# Sheetlaba1.net
KiCad netlist of a schematic drawn in Altium Designer
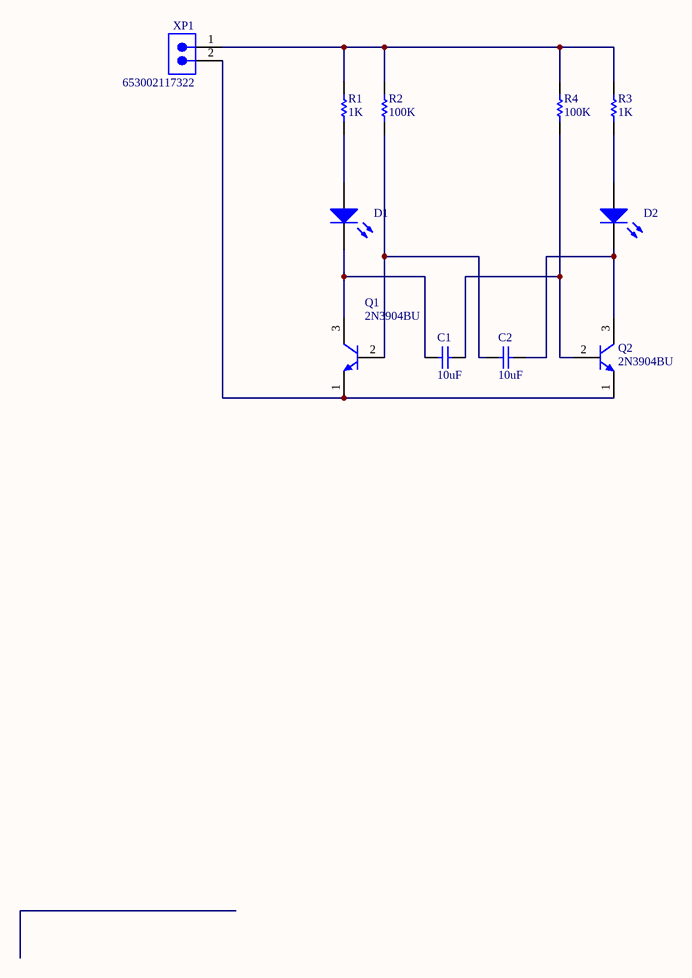
[diagram p0: Sheetlaba1.SchDoc]

(export (version "E")
  (design (tool "Eeschema 10.0.6"))
  (components
    (comp (ref "C1")
      (value "10uF")
      (description "Capacitor")
      (libsource (lib "Simulation Generic Components") (part "Capacitor"))
    )
    (comp (ref "C2")
      (value "10uF")
      (description "Capacitor")
      (libsource (lib "Simulation Generic Components") (part "Capacitor"))
    )
    (comp (ref "D1")
      (value "Light-Emitting Diode")
      (libsource (lib "Simulation Generic Components") (part "LED"))
    )
    (comp (ref "D2")
      (value "Light-Emitting Diode")
      (libsource (lib "Simulation Generic Components") (part "LED"))
    )
    (comp (ref "Q1")
      (value "2N3904BU")
      (footprint "FAIR-TO-92")
      (description "NPN General-Purpose Amplifier, 40 V VCEO, 0.2 A, -55 to 150 degC, 2-Pin TO-92, RoHS, Bulk")
      (fields (field (name "MANUFACTURER") "FairchildSemiconductor"))
      (libsource (lib "Altium Content Vault") (part "NPN-E1B2C3-3"))
    )
    (comp (ref "Q2")
      (value "2N3904BU")
      (footprint "FAIR-TO-92")
      (description "NPN General-Purpose Amplifier, 40 V VCEO, 0.2 A, -55 to 150 degC, 2-Pin TO-92, RoHS, Bulk")
      (fields (field (name "MANUFACTURER") "FairchildSemiconductor"))
      (libsource (lib "Altium Content Vault") (part "NPN-E1B2C3-3"))
    )
    (comp (ref "R1")
      (value "1K")
      (description "Resistor")
      (libsource (lib "Simulation Generic Components") (part "Resistor"))
    )
    (comp (ref "R2")
      (value "100K")
      (description "Resistor")
      (libsource (lib "Simulation Generic Components") (part "Resistor"))
    )
    (comp (ref "R3")
      (value "1K")
      (description "Resistor")
      (libsource (lib "Simulation Generic Components") (part "Resistor"))
    )
    (comp (ref "R4")
      (value "100K")
      (description "Resistor")
      (libsource (lib "Simulation Generic Components") (part "Resistor"))
    )
    (comp (ref "XP1")
      (value "653002117322")
      (footprint "653002117322")
      (description "Conn, R/A Header, 2Pos, 1Row, 1.25Mm Rohs Compliant: Yes")
      (libsource (lib "Altium Content Vault") (part "Header_Male_1R_02P"))
    )
  )
  (nets
    (net (code "1") (name "Net-(D1-A)") (class "Default")
      (node (ref "D1") (pin "1") (pinfunction "A_1") (pintype "passive"))
      (node (ref "R1") (pin "2") (pinfunction "2_2") (pintype "passive"))
    )
    (net (code "2") (name "Net-(D1-K)") (class "Default")
      (node (ref "C1") (pin "2") (pinfunction "2_2") (pintype "passive"))
      (node (ref "D1") (pin "2") (pinfunction "K_2") (pintype "passive"))
      (node (ref "Q1") (pin "3") (pinfunction "C_3") (pintype "passive"))
    )
    (net (code "3") (name "Net-(D2-A)") (class "Default")
      (node (ref "D2") (pin "1") (pinfunction "A_1") (pintype "passive"))
      (node (ref "R3") (pin "1") (pinfunction "1_1") (pintype "passive"))
    )
    (net (code "4") (name "Net-(D2-K)") (class "Default")
      (node (ref "C2") (pin "1") (pinfunction "1_1") (pintype "passive"))
      (node (ref "D2") (pin "2") (pinfunction "K_2") (pintype "passive"))
      (node (ref "Q2") (pin "3") (pinfunction "C_3") (pintype "passive"))
    )
    (net (code "5") (name "Net-(Q1-B)") (class "Default")
      (node (ref "C2") (pin "2") (pinfunction "2_2") (pintype "passive"))
      (node (ref "Q1") (pin "2") (pinfunction "B_2") (pintype "passive"))
      (node (ref "R2") (pin "2") (pinfunction "2_2") (pintype "passive"))
    )
    (net (code "6") (name "Net-(Q1-E)") (class "Default")
      (node (ref "Q1") (pin "1") (pinfunction "E_1") (pintype "passive"))
      (node (ref "Q2") (pin "1") (pinfunction "E_1") (pintype "passive"))
      (node (ref "XP1") (pin "2") (pinfunction "2_2") (pintype "passive"))
    )
    (net (code "7") (name "Net-(Q2-B)") (class "Default")
      (node (ref "C1") (pin "1") (pinfunction "1_1") (pintype "passive"))
      (node (ref "Q2") (pin "2") (pinfunction "B_2") (pintype "passive"))
      (node (ref "R4") (pin "1") (pinfunction "1_1") (pintype "passive"))
    )
    (net (code "8") (name "Net-(R1-Pad1)") (class "Default")
      (node (ref "R1") (pin "1") (pinfunction "1_1") (pintype "passive"))
      (node (ref "R2") (pin "1") (pinfunction "1_1") (pintype "passive"))
      (node (ref "R3") (pin "2") (pinfunction "2_2") (pintype "passive"))
      (node (ref "R4") (pin "2") (pinfunction "2_2") (pintype "passive"))
      (node (ref "XP1") (pin "1") (pinfunction "1_1") (pintype "passive"))
    )
  )
)
